# BinMonitored.net
KiCad netlist of a schematic drawn in EAGLE
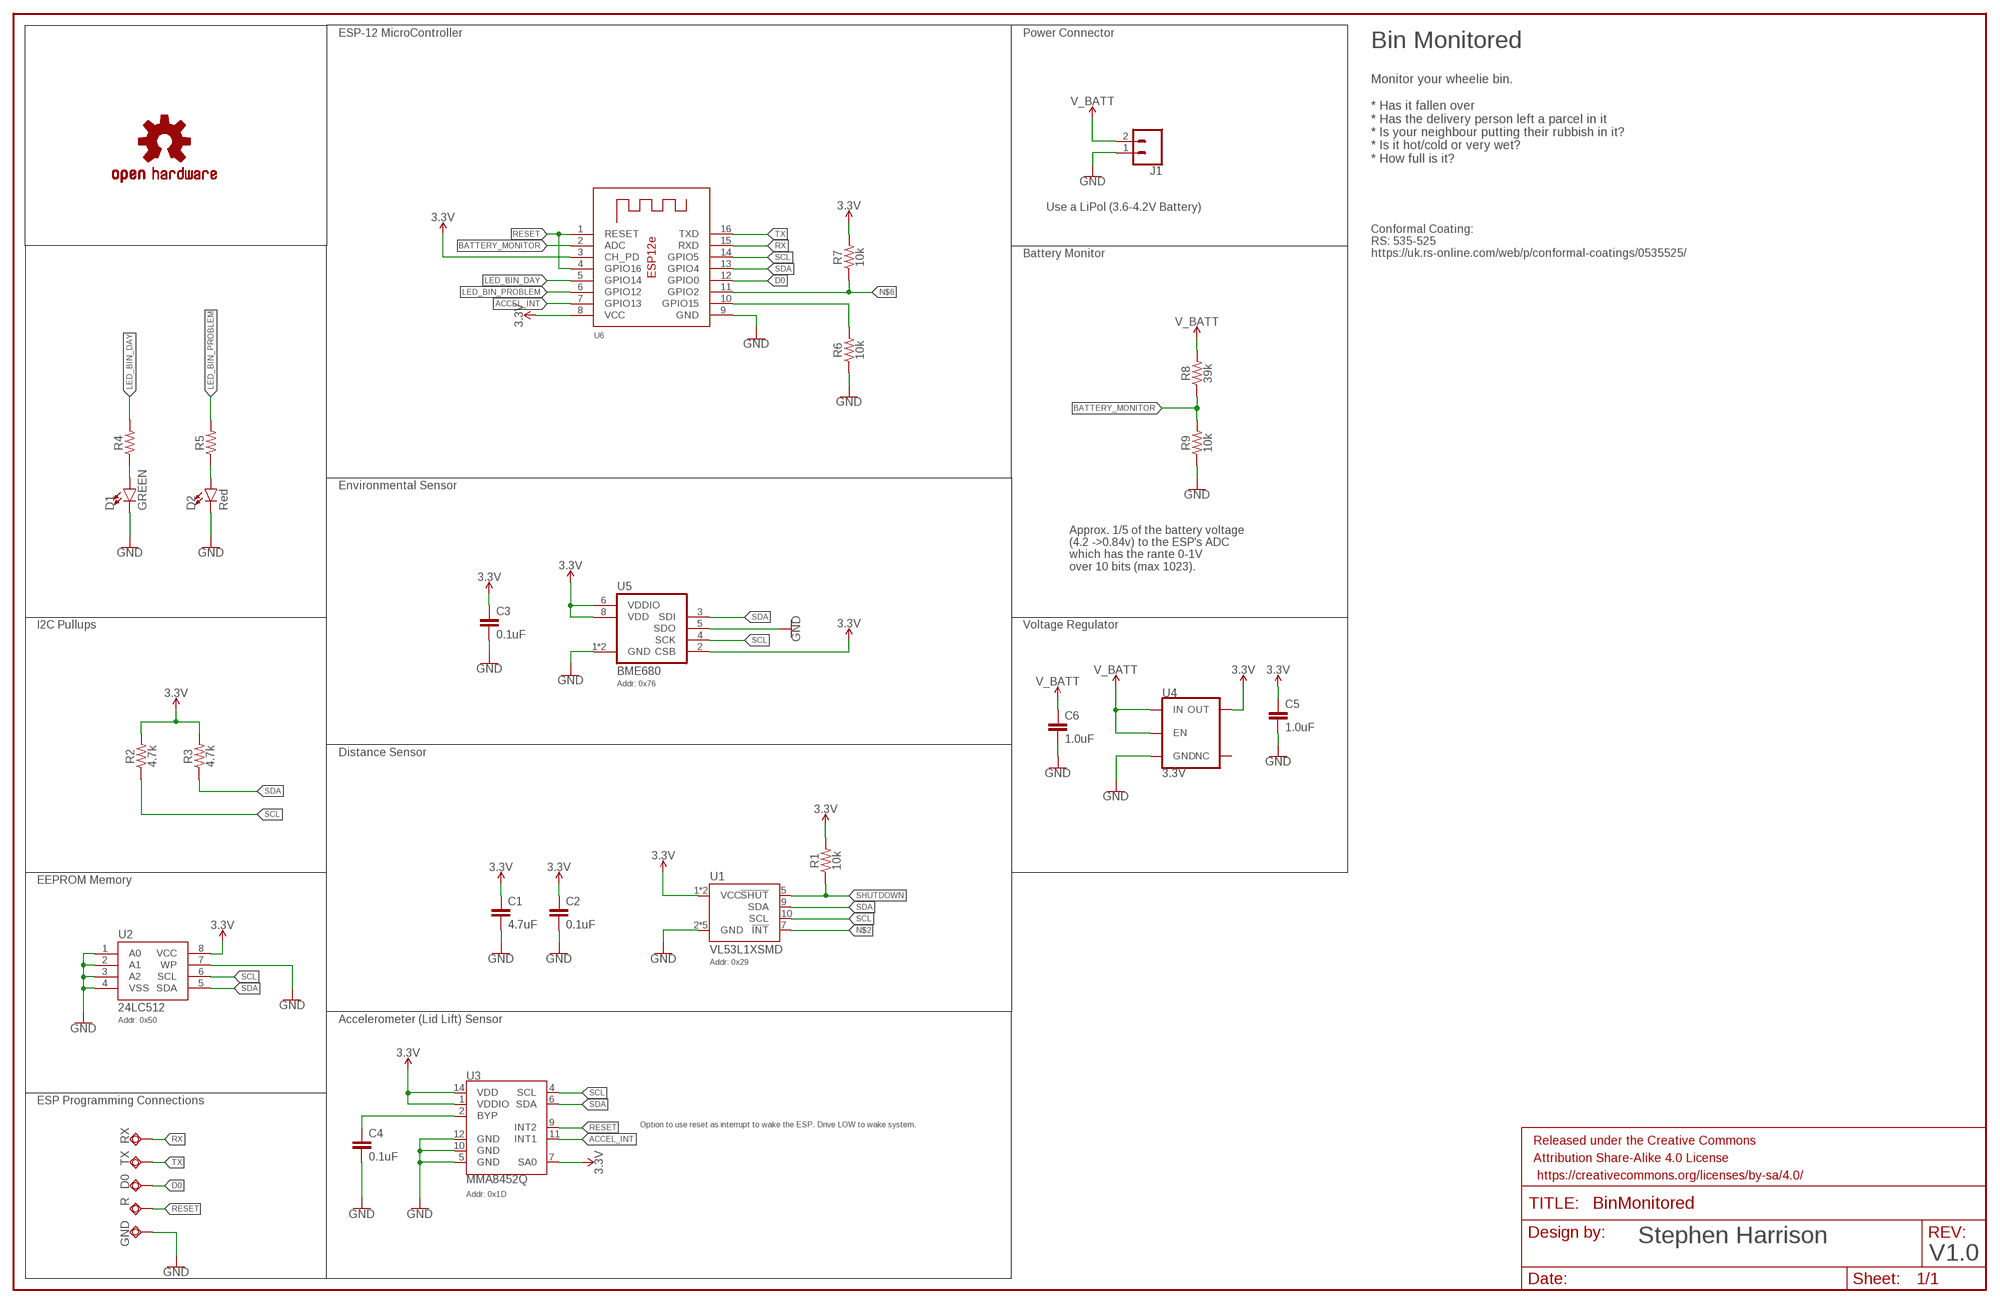
[diagram p0: schematic, sheet 1]

(export (version "E")
  (design (tool "Eeschema 10.0.6"))
  (components
    (comp (ref "C1")
      (value "4.7uF")
      (footprint "eagle-import:0603")
      (libsource (lib "eagle-import") (part "4.7UF-0603-6.3V-(10%)"))
    )
    (comp (ref "C2")
      (value "0.1uF")
      (footprint "eagle-import:0603")
      (libsource (lib "eagle-import") (part "0.1UF-0603-25V-5%"))
    )
    (comp (ref "C3")
      (value "0.1uF")
      (footprint "eagle-import:0603")
      (libsource (lib "eagle-import") (part "0.1UF-0603-25V-5%"))
    )
    (comp (ref "C4")
      (value "0.1uF")
      (footprint "eagle-import:0603")
      (libsource (lib "eagle-import") (part "0.1UF-0603-25V-5%"))
    )
    (comp (ref "C5")
      (value "1.0uF")
      (footprint "eagle-import:0603")
      (libsource (lib "eagle-import") (part "0.1UF-0603-25V-5%"))
    )
    (comp (ref "C6")
      (value "1.0uF")
      (footprint "eagle-import:0603")
      (libsource (lib "eagle-import") (part "0.1UF-0603-25V-5%"))
    )
    (comp (ref "D0")
      (value "TPSQTP10SQ")
      (footprint "eagle-import:TP10SQ")
      (libsource (lib "eagle-import") (part "TPSQTP10SQ"))
    )
    (comp (ref "D1")
      (value "GREEN")
      (footprint "eagle-import:LED-1206")
      (libsource (lib "eagle-import") (part "LED-GREEN1206"))
    )
    (comp (ref "D2")
      (value "Red")
      (footprint "eagle-import:LED-1206")
      (libsource (lib "eagle-import") (part "LED-GREEN1206"))
    )
    (comp (ref "FRAME1")
      (value "FRAME-LEDGER")
      (footprint "eagle-import:CREATIVE_COMMONS")
      (libsource (lib "eagle-import") (part "FRAME-LEDGER"))
    )
    (comp (ref "GND")
      (value "TPSQTP10SQ")
      (footprint "eagle-import:TP10SQ")
      (libsource (lib "eagle-import") (part "TPSQTP10SQ"))
    )
    (comp (ref "J1")
      (value "CONN_02-JST-2MM-SMT")
      (footprint "eagle-import:JST-2-SMD")
      (libsource (lib "eagle-import") (part "CONN_02-JST-2MM-SMT"))
    )
    (comp (ref "LOGO1")
      (value "OSHW-LOGOL")
      (footprint "eagle-import:OSHW-LOGO-L")
      (libsource (lib "eagle-import") (part "OSHW-LOGOL"))
    )
    (comp (ref "R")
      (value "TPSQTP10SQ")
      (footprint "eagle-import:TP10SQ")
      (libsource (lib "eagle-import") (part "TPSQTP10SQ"))
    )
    (comp (ref "R1")
      (value "10k")
      (footprint "eagle-import:0603")
      (libsource (lib "eagle-import") (part "10KOHM-0603-1/10W-1%"))
    )
    (comp (ref "R2")
      (value "4.7k")
      (footprint "eagle-import:0603")
      (libsource (lib "eagle-import") (part "4.7KOHM-0603-1/10W-1%"))
    )
    (comp (ref "R3")
      (value "4.7k")
      (footprint "eagle-import:0603")
      (libsource (lib "eagle-import") (part "4.7KOHM-0603-1/10W-1%"))
    )
    (comp (ref "R4")
      (value "RESISTOR0805")
      (footprint "eagle-import:0805")
      (libsource (lib "eagle-import") (part "RESISTOR0805"))
    )
    (comp (ref "R5")
      (value "RESISTOR0805")
      (footprint "eagle-import:0805")
      (libsource (lib "eagle-import") (part "RESISTOR0805"))
    )
    (comp (ref "R6")
      (value "10k")
      (footprint "eagle-import:0603")
      (libsource (lib "eagle-import") (part "10KOHM-0603-1/10W-1%"))
    )
    (comp (ref "R7")
      (value "10k")
      (footprint "eagle-import:0603")
      (libsource (lib "eagle-import") (part "10KOHM-0603-1/10W-1%"))
    )
    (comp (ref "R8")
      (value "39k")
      (footprint "eagle-import:0603")
      (libsource (lib "eagle-import") (part "RESISTOR0603"))
    )
    (comp (ref "R9")
      (value "10k")
      (footprint "eagle-import:0603")
      (libsource (lib "eagle-import") (part "RESISTOR0603"))
    )
    (comp (ref "RX")
      (value "TPSQTP10SQ")
      (footprint "eagle-import:TP10SQ")
      (libsource (lib "eagle-import") (part "TPSQTP10SQ"))
    )
    (comp (ref "TX")
      (value "TPSQTP10SQ")
      (footprint "eagle-import:TP10SQ")
      (libsource (lib "eagle-import") (part "TPSQTP10SQ"))
    )
    (comp (ref "U1")
      (value "VL53L1XSMD")
      (footprint "eagle-import:VL53L1X")
      (libsource (lib "eagle-import") (part "VL53L1XSMD"))
    )
    (comp (ref "U2")
      (value "24LC512")
      (footprint "eagle-import:SO08")
      (libsource (lib "eagle-import") (part "EEPROM-I2CSMD"))
    )
    (comp (ref "U3")
      (value "MMA8452Q")
      (footprint "eagle-import:QFN-16")
      (libsource (lib "eagle-import") (part "MMA8452Q"))
    )
    (comp (ref "U4")
      (value "3.3V")
      (footprint "eagle-import:SOT23-5")
      (libsource (lib "eagle-import") (part "V_REG_AP2112K-3.3V"))
    )
    (comp (ref "U5")
      (value "BME680")
      (footprint "eagle-import:BME680")
      (libsource (lib "eagle-import") (part "BME680"))
    )
    (comp (ref "U6")
      (value "ESP-12E")
      (footprint "eagle-import:ESP-12E")
      (libsource (lib "eagle-import") (part "ESP-12E"))
    )
  )
  (nets
    (net (code "1") (name "3.3V") (class "Default")
      (node (ref "C1") (pin "1") (pinfunction "1_1") (pintype "passive"))
      (node (ref "C2") (pin "1") (pinfunction "1_1") (pintype "passive"))
      (node (ref "C3") (pin "1") (pinfunction "1_1") (pintype "passive"))
      (node (ref "C5") (pin "1") (pinfunction "1_1") (pintype "passive"))
      (node (ref "R1") (pin "2") (pinfunction "2_2") (pintype "passive"))
      (node (ref "R2") (pin "2") (pinfunction "2_2") (pintype "passive"))
      (node (ref "R3") (pin "2") (pinfunction "2_2") (pintype "passive"))
      (node (ref "R7") (pin "2") (pinfunction "2_2") (pintype "passive"))
      (node (ref "U1") (pin "1") (pinfunction "VCC_1") (pintype "bidirectional"))
      (node (ref "U1") (pin "11") (pinfunction "VCC_11") (pintype "bidirectional"))
      (node (ref "U2") (pin "8") (pinfunction "VCC_8") (pintype "power_in"))
      (node (ref "U3") (pin "1") (pinfunction "VDDIO_1") (pintype "bidirectional"))
      (node (ref "U3") (pin "14") (pinfunction "VDD_14") (pintype "bidirectional"))
      (node (ref "U3") (pin "7") (pinfunction "SA0_7") (pintype "bidirectional"))
      (node (ref "U4") (pin "5") (pinfunction "OUT_5") (pintype "passive"))
      (node (ref "U5") (pin "2") (pinfunction "CSB_2") (pintype "input"))
      (node (ref "U5") (pin "6") (pinfunction "VDDIO_6") (pintype "power_in"))
      (node (ref "U5") (pin "8") (pinfunction "VDD_8") (pintype "power_in"))
      (node (ref "U6") (pin "3") (pinfunction "CH_PD_3") (pintype "input"))
      (node (ref "U6") (pin "8") (pinfunction "VCC_8") (pintype "power_in"))
    )
    (net (code "2") (name "ACCEL_INT") (class "Default")
      (node (ref "U3") (pin "11") (pinfunction "INT1_11") (pintype "bidirectional"))
      (node (ref "U6") (pin "7") (pinfunction "GPIO13_7") (pintype "bidirectional"))
    )
    (net (code "3") (name "BATTERY_MONITOR") (class "Default")
      (node (ref "R8") (pin "1") (pinfunction "1_1") (pintype "passive"))
      (node (ref "R9") (pin "2") (pinfunction "2_2") (pintype "passive"))
      (node (ref "U6") (pin "2") (pinfunction "ADC_2") (pintype "passive"))
    )
    (net (code "4") (name "D0") (class "Default")
      (node (ref "D0") (pin "TP") (pinfunction "TP_TP") (pintype "input"))
      (node (ref "U6") (pin "12") (pinfunction "GPIO0_12") (pintype "bidirectional"))
    )
    (net (code "5") (name "GND") (class "Default")
      (node (ref "C1") (pin "2") (pinfunction "2_2") (pintype "passive"))
      (node (ref "C2") (pin "2") (pinfunction "2_2") (pintype "passive"))
      (node (ref "C3") (pin "2") (pinfunction "2_2") (pintype "passive"))
      (node (ref "C4") (pin "2") (pinfunction "2_2") (pintype "passive"))
      (node (ref "C5") (pin "2") (pinfunction "2_2") (pintype "passive"))
      (node (ref "C6") (pin "2") (pinfunction "2_2") (pintype "passive"))
      (node (ref "D1") (pin "C") (pinfunction "C_C") (pintype "passive"))
      (node (ref "D2") (pin "C") (pinfunction "C_C") (pintype "passive"))
      (node (ref "GND") (pin "TP") (pinfunction "TP_TP") (pintype "input"))
      (node (ref "J1") (pin "1") (pinfunction "2_1") (pintype "passive"))
      (node (ref "R6") (pin "1") (pinfunction "1_1") (pintype "passive"))
      (node (ref "R9") (pin "1") (pinfunction "1_1") (pintype "passive"))
      (node (ref "U1") (pin "12") (pinfunction "GND_12") (pintype "bidirectional"))
      (node (ref "U1") (pin "2") (pinfunction "GND_2") (pintype "bidirectional"))
      (node (ref "U1") (pin "3") (pinfunction "GND_3") (pintype "bidirectional"))
      (node (ref "U1") (pin "4") (pinfunction "GND_4") (pintype "bidirectional"))
      (node (ref "U1") (pin "6") (pinfunction "GND_6") (pintype "bidirectional"))
      (node (ref "U2") (pin "1") (pinfunction "A0_1") (pintype "bidirectional"))
      (node (ref "U2") (pin "2") (pinfunction "A1_2") (pintype "bidirectional"))
      (node (ref "U2") (pin "3") (pinfunction "A2_3") (pintype "bidirectional"))
      (node (ref "U2") (pin "4") (pinfunction "VSS_4") (pintype "power_in"))
      (node (ref "U2") (pin "7") (pinfunction "WP_7") (pintype "bidirectional"))
      (node (ref "U3") (pin "10") (pinfunction "GND_10") (pintype "bidirectional"))
      (node (ref "U3") (pin "12") (pinfunction "GND_12") (pintype "bidirectional"))
      (node (ref "U3") (pin "5") (pinfunction "GND_5") (pintype "bidirectional"))
      (node (ref "U4") (pin "2") (pinfunction "GND_2") (pintype "input"))
      (node (ref "U5") (pin "1") (pinfunction "GND_1") (pintype "power_in"))
      (node (ref "U5") (pin "5") (pinfunction "SDO_5") (pintype "output"))
      (node (ref "U5") (pin "7") (pinfunction "GND_7") (pintype "power_in"))
      (node (ref "U6") (pin "9") (pinfunction "GND_9") (pintype "power_in"))
    )
    (net (code "6") (name "LED_BIN_DAY") (class "Default")
      (node (ref "R4") (pin "2") (pinfunction "2_2") (pintype "passive"))
      (node (ref "U6") (pin "5") (pinfunction "GPIO14_5") (pintype "bidirectional"))
    )
    (net (code "7") (name "LED_BIN_PROBLEM") (class "Default")
      (node (ref "R5") (pin "2") (pinfunction "2_2") (pintype "passive"))
      (node (ref "U6") (pin "6") (pinfunction "GPIO12_6") (pintype "bidirectional"))
    )
    (net (code "8") (name "N$2") (class "Default")
      (node (ref "U1") (pin "7") (pinfunction "~{INT}_7") (pintype "bidirectional"))
    )
    (net (code "9") (name "N$6") (class "Default")
      (node (ref "R7") (pin "1") (pinfunction "1_1") (pintype "passive"))
      (node (ref "U6") (pin "11") (pinfunction "GPIO2_11") (pintype "bidirectional"))
    )
    (net (code "10") (name "Net-(D1-PadA)") (class "Default")
      (node (ref "D1") (pin "A") (pinfunction "A_A") (pintype "passive"))
      (node (ref "R4") (pin "1") (pinfunction "1_1") (pintype "passive"))
    )
    (net (code "11") (name "Net-(D2-PadA)") (class "Default")
      (node (ref "D2") (pin "A") (pinfunction "A_A") (pintype "passive"))
      (node (ref "R5") (pin "1") (pinfunction "1_1") (pintype "passive"))
    )
    (net (code "12") (name "Net-(U3-BYP)") (class "Default")
      (node (ref "C4") (pin "1") (pinfunction "1_1") (pintype "passive"))
      (node (ref "U3") (pin "2") (pinfunction "BYP_2") (pintype "bidirectional"))
    )
    (net (code "13") (name "Net-(U6-GPIO15)") (class "Default")
      (node (ref "R6") (pin "2") (pinfunction "2_2") (pintype "passive"))
      (node (ref "U6") (pin "10") (pinfunction "GPIO15_10") (pintype "bidirectional"))
    )
    (net (code "14") (name "RESET") (class "Default")
      (node (ref "R") (pin "TP") (pinfunction "TP_TP") (pintype "input"))
      (node (ref "U3") (pin "9") (pinfunction "INT2_9") (pintype "bidirectional"))
      (node (ref "U6") (pin "1") (pinfunction "RESET_1") (pintype "input"))
      (node (ref "U6") (pin "4") (pinfunction "GPIO16_4") (pintype "bidirectional"))
    )
    (net (code "15") (name "RX") (class "Default")
      (node (ref "RX") (pin "TP") (pinfunction "TP_TP") (pintype "input"))
      (node (ref "U6") (pin "15") (pinfunction "RXD_15") (pintype "input"))
    )
    (net (code "16") (name "SCL") (class "Default")
      (node (ref "R2") (pin "1") (pinfunction "1_1") (pintype "passive"))
      (node (ref "U1") (pin "10") (pinfunction "SCL_10") (pintype "bidirectional"))
      (node (ref "U2") (pin "6") (pinfunction "SCL_6") (pintype "bidirectional"))
      (node (ref "U3") (pin "4") (pinfunction "SCL_4") (pintype "bidirectional"))
      (node (ref "U5") (pin "4") (pinfunction "SCK_4") (pintype "input"))
      (node (ref "U6") (pin "14") (pinfunction "GPIO5_14") (pintype "bidirectional"))
    )
    (net (code "17") (name "SDA") (class "Default")
      (node (ref "R3") (pin "1") (pinfunction "1_1") (pintype "passive"))
      (node (ref "U1") (pin "9") (pinfunction "SDA_9") (pintype "bidirectional"))
      (node (ref "U2") (pin "5") (pinfunction "SDA_5") (pintype "bidirectional"))
      (node (ref "U3") (pin "6") (pinfunction "SDA_6") (pintype "bidirectional"))
      (node (ref "U5") (pin "3") (pinfunction "SDI_3") (pintype "input"))
      (node (ref "U6") (pin "13") (pinfunction "GPIO4_13") (pintype "bidirectional"))
    )
    (net (code "18") (name "SHUTDOWN") (class "Default")
      (node (ref "R1") (pin "1") (pinfunction "1_1") (pintype "passive"))
      (node (ref "U1") (pin "5") (pinfunction "~{SHUT}_5") (pintype "bidirectional"))
    )
    (net (code "19") (name "TX") (class "Default")
      (node (ref "TX") (pin "TP") (pinfunction "TP_TP") (pintype "input"))
      (node (ref "U6") (pin "16") (pinfunction "TXD_16") (pintype "output"))
    )
    (net (code "20") (name "V_BATT") (class "Default")
      (node (ref "C6") (pin "1") (pinfunction "1_1") (pintype "passive"))
      (node (ref "J1") (pin "2") (pinfunction "1_2") (pintype "passive"))
      (node (ref "R8") (pin "2") (pinfunction "2_2") (pintype "passive"))
      (node (ref "U4") (pin "1") (pinfunction "IN_1") (pintype "input"))
      (node (ref "U4") (pin "3") (pinfunction "EN_3") (pintype "input"))
    )
    (net (code "21") (name "unconnected-(U4-NC-Pad4)") (class "Default")
      (node (ref "U4") (pin "4") (pinfunction "NC_4") (pintype "no_connect"))
    )
  )
)
